# wt11_breakout_board_v10.net
KiCad netlist of a schematic drawn in EAGLE
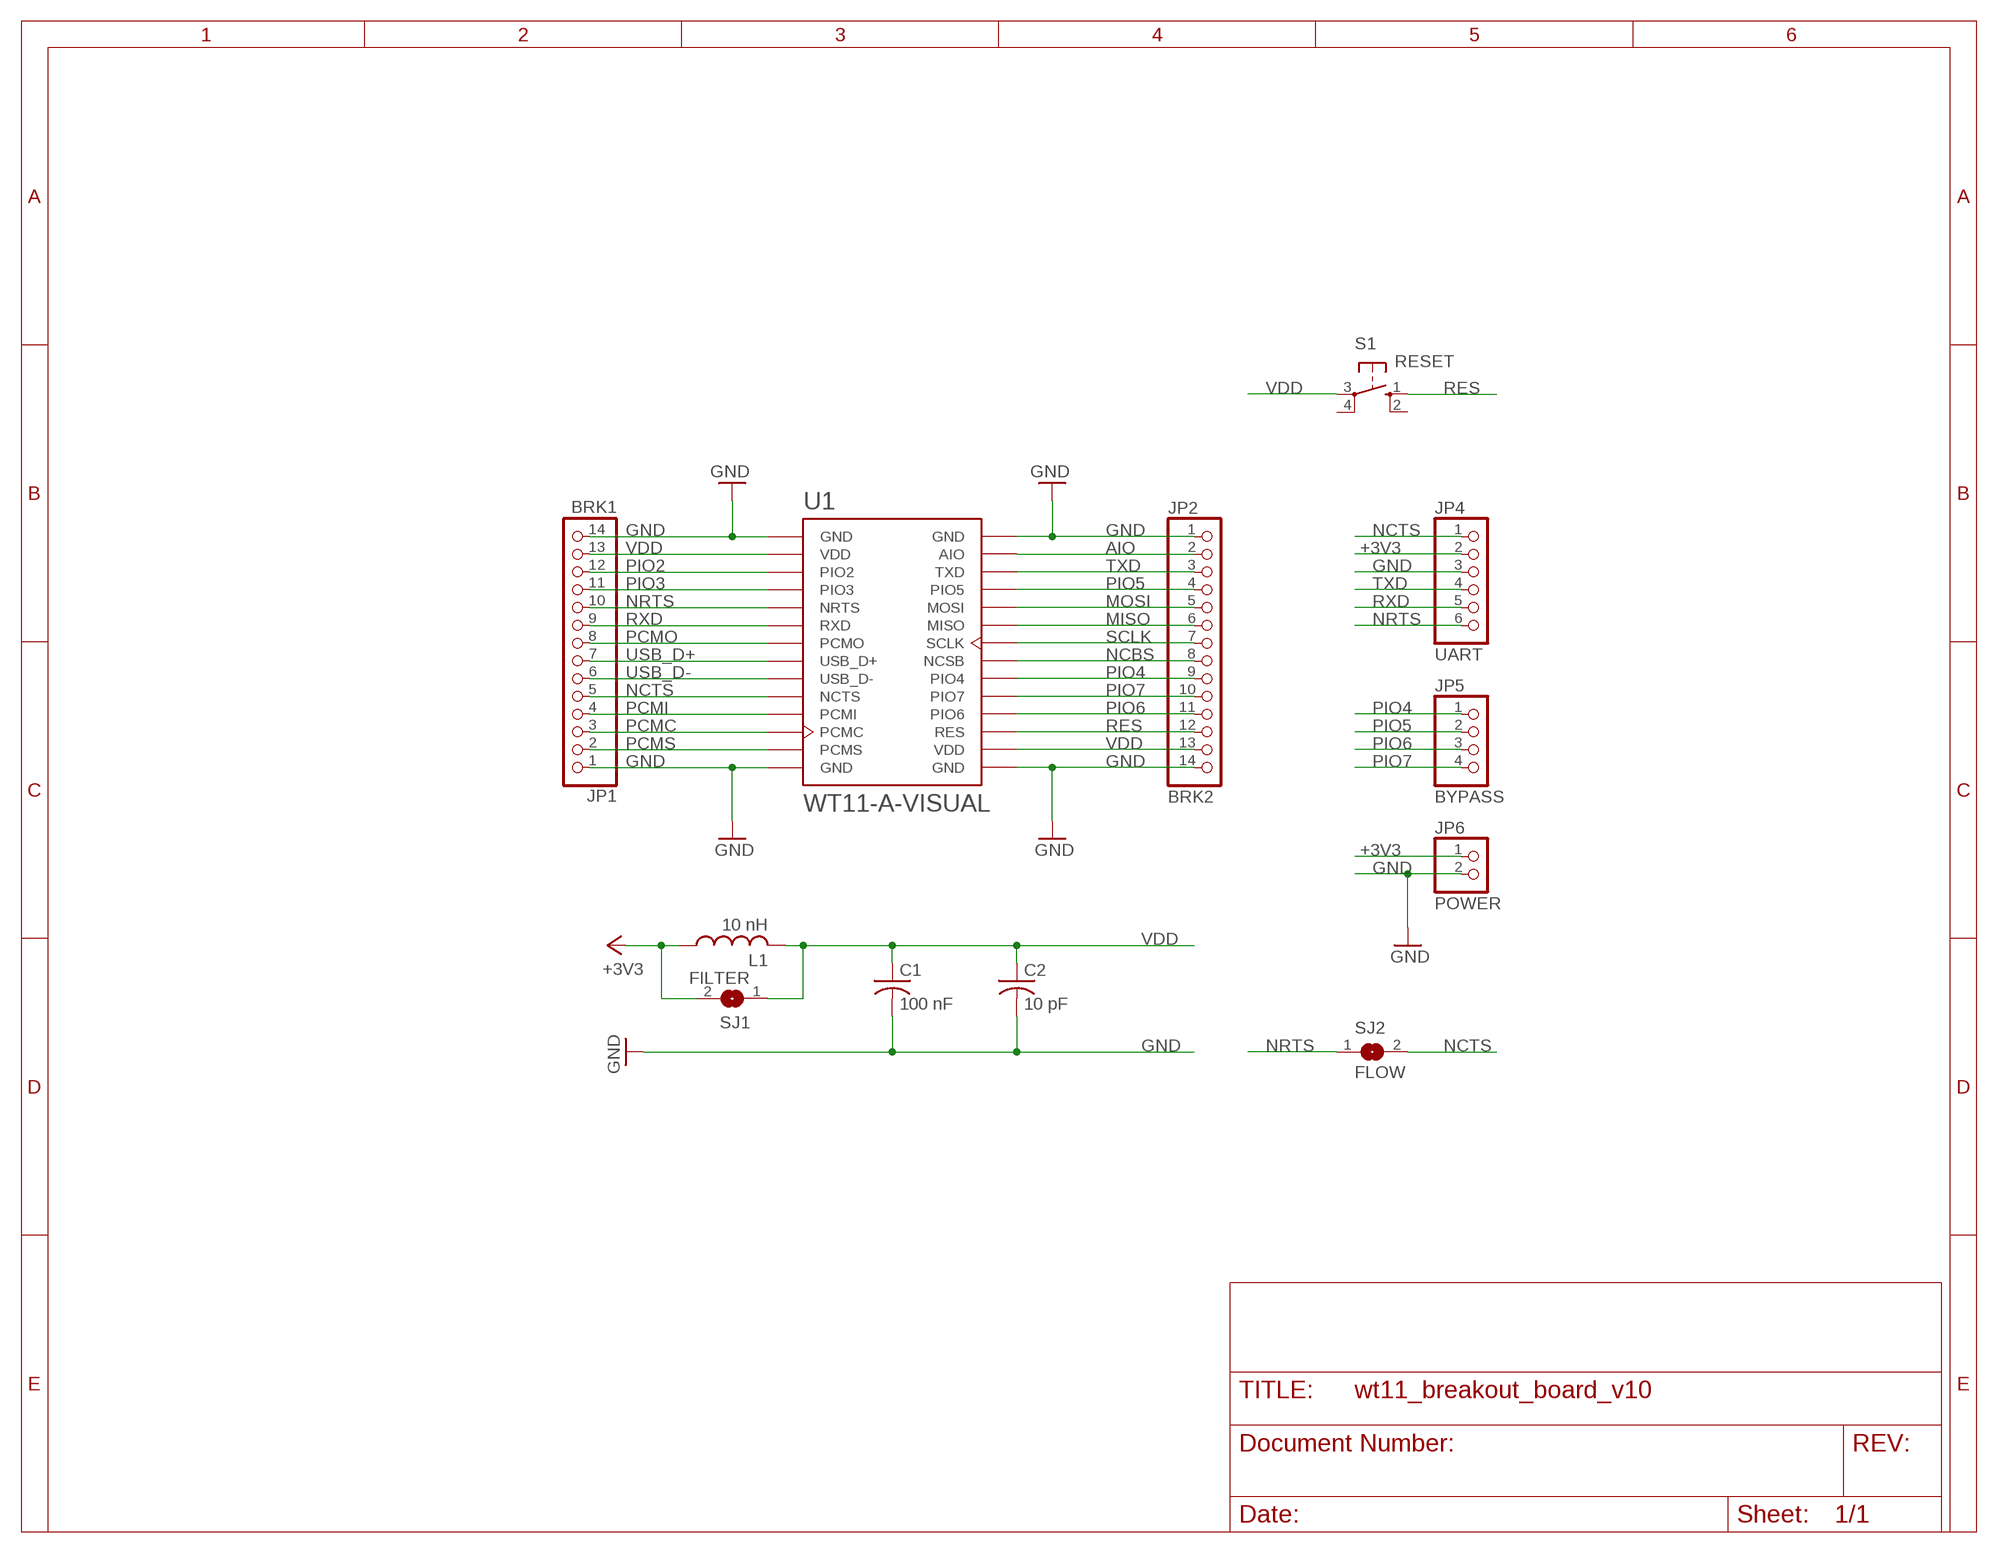
[diagram p0: schematic, sheet 1]

(export (version "E")
  (design (tool "Eeschema 10.0.6"))
  (components
    (comp (ref "C1")
      (value "100 nF")
      (footprint "eagle-import:C025-025X050")
      (libsource (lib "eagle-import") (part "C-US025-025X050"))
    )
    (comp (ref "C2")
      (value "10 pF")
      (footprint "eagle-import:C025-025X050")
      (libsource (lib "eagle-import") (part "C-US025-025X050"))
    )
    (comp (ref "JP1")
      (value "BRK1")
      (footprint "eagle-import:1X14")
      (libsource (lib "eagle-import") (part "PINHD-1X14"))
    )
    (comp (ref "JP2")
      (value "BRK2")
      (footprint "eagle-import:1X14")
      (libsource (lib "eagle-import") (part "PINHD-1X14"))
    )
    (comp (ref "JP4")
      (value "UART")
      (footprint "eagle-import:1X06")
      (libsource (lib "eagle-import") (part "PINHD-1X6"))
    )
    (comp (ref "JP5")
      (value "BYPASS")
      (footprint "eagle-import:1X04")
      (libsource (lib "eagle-import") (part "PINHD-1X4"))
    )
    (comp (ref "JP6")
      (value "POWER")
      (footprint "eagle-import:1X02")
      (libsource (lib "eagle-import") (part "PINHD-1X2"))
    )
    (comp (ref "L1")
      (value "10 nH")
      (footprint "eagle-import:0204_7")
      (libsource (lib "eagle-import") (part "L-US0204/7"))
    )
    (comp (ref "S1")
      (value "RESET")
      (footprint "eagle-import:B3F-10XX")
      (fields (field (name "MPN") "B3F-1000"))
      (libsource (lib "eagle-import") (part "10-XX"))
    )
    (comp (ref "SJ1")
      (value "FILTER")
      (footprint "eagle-import:SJ")
      (libsource (lib "eagle-import") (part "SJ"))
    )
    (comp (ref "SJ2")
      (value "FLOW")
      (footprint "eagle-import:SJ")
      (libsource (lib "eagle-import") (part "SJ"))
    )
    (comp (ref "U1")
      (value "WT11-A-VISUAL")
      (footprint "eagle-import:WT11-A")
      (libsource (lib "eagle-import") (part "WT11-A-VISUAL"))
    )
  )
  (nets
    (net (code "1") (name "+3V3") (class "Default")
      (node (ref "JP4") (pin "2") (pinfunction "2_2") (pintype "passive"))
      (node (ref "JP6") (pin "1") (pinfunction "1_1") (pintype "passive"))
      (node (ref "L1") (pin "1") (pinfunction "1_1") (pintype "passive"))
      (node (ref "SJ1") (pin "2") (pinfunction "2_2") (pintype "passive"))
    )
    (net (code "2") (name "/AIO") (class "Default")
      (node (ref "JP2") (pin "2") (pinfunction "2_2") (pintype "passive"))
      (node (ref "U1") (pin "AIO") (pinfunction "AIO_AIO") (pintype "bidirectional"))
    )
    (net (code "3") (name "/MISO") (class "Default")
      (node (ref "JP2") (pin "6") (pinfunction "6_6") (pintype "passive"))
      (node (ref "U1") (pin "MISO") (pinfunction "MISO_MISO") (pintype "output"))
    )
    (net (code "4") (name "/MOSI") (class "Default")
      (node (ref "JP2") (pin "5") (pinfunction "5_5") (pintype "passive"))
      (node (ref "U1") (pin "MOSI") (pinfunction "MOSI_MOSI") (pintype "input"))
    )
    (net (code "5") (name "/NCBS") (class "Default")
      (node (ref "JP2") (pin "8") (pinfunction "8_8") (pintype "passive"))
      (node (ref "U1") (pin "NCSB") (pinfunction "NCSB_NCSB") (pintype "input"))
    )
    (net (code "6") (name "/NCTS") (class "Default")
      (node (ref "JP1") (pin "5") (pinfunction "5_5") (pintype "passive"))
      (node (ref "JP4") (pin "1") (pinfunction "1_1") (pintype "passive"))
      (node (ref "SJ2") (pin "2") (pinfunction "2_2") (pintype "passive"))
      (node (ref "U1") (pin "NCTS") (pinfunction "NCTS_NCTS") (pintype "input"))
    )
    (net (code "7") (name "/NRTS") (class "Default")
      (node (ref "JP1") (pin "10") (pinfunction "10_10") (pintype "passive"))
      (node (ref "JP4") (pin "6") (pinfunction "6_6") (pintype "passive"))
      (node (ref "SJ2") (pin "1") (pinfunction "1_1") (pintype "passive"))
      (node (ref "U1") (pin "NRTS") (pinfunction "NRTS_NRTS") (pintype "output"))
    )
    (net (code "8") (name "/PCMC") (class "Default")
      (node (ref "JP1") (pin "3") (pinfunction "3_3") (pintype "passive"))
      (node (ref "U1") (pin "PCMC") (pinfunction "PCMC_PCMC") (pintype "bidirectional"))
    )
    (net (code "9") (name "/PCMI") (class "Default")
      (node (ref "JP1") (pin "4") (pinfunction "4_4") (pintype "passive"))
      (node (ref "U1") (pin "PCMI") (pinfunction "PCMI_PCMI") (pintype "input"))
    )
    (net (code "10") (name "/PCMO") (class "Default")
      (node (ref "JP1") (pin "8") (pinfunction "8_8") (pintype "passive"))
      (node (ref "U1") (pin "PCMO") (pinfunction "PCMO_PCMO") (pintype "output"))
    )
    (net (code "11") (name "/PCMS") (class "Default")
      (node (ref "JP1") (pin "2") (pinfunction "2_2") (pintype "passive"))
      (node (ref "U1") (pin "PCMS") (pinfunction "PCMS_PCMS") (pintype "bidirectional"))
    )
    (net (code "12") (name "/PIO2") (class "Default")
      (node (ref "JP1") (pin "12") (pinfunction "12_12") (pintype "passive"))
      (node (ref "U1") (pin "PIO2") (pinfunction "PIO2_PIO2") (pintype "bidirectional"))
    )
    (net (code "13") (name "/PIO3") (class "Default")
      (node (ref "JP1") (pin "11") (pinfunction "11_11") (pintype "passive"))
      (node (ref "U1") (pin "PIO3") (pinfunction "PIO3_PIO3") (pintype "bidirectional"))
    )
    (net (code "14") (name "/PIO4") (class "Default")
      (node (ref "JP2") (pin "9") (pinfunction "9_9") (pintype "passive"))
      (node (ref "JP5") (pin "1") (pinfunction "1_1") (pintype "passive"))
      (node (ref "U1") (pin "PIO4") (pinfunction "PIO4_PIO4") (pintype "bidirectional"))
    )
    (net (code "15") (name "/PIO5") (class "Default")
      (node (ref "JP2") (pin "4") (pinfunction "4_4") (pintype "passive"))
      (node (ref "JP5") (pin "2") (pinfunction "2_2") (pintype "passive"))
      (node (ref "U1") (pin "PIO5") (pinfunction "PIO5_PIO5") (pintype "bidirectional"))
    )
    (net (code "16") (name "/PIO6") (class "Default")
      (node (ref "JP2") (pin "11") (pinfunction "11_11") (pintype "passive"))
      (node (ref "JP5") (pin "3") (pinfunction "3_3") (pintype "passive"))
      (node (ref "U1") (pin "PIO6") (pinfunction "PIO6_PIO6") (pintype "bidirectional"))
    )
    (net (code "17") (name "/PIO7") (class "Default")
      (node (ref "JP2") (pin "10") (pinfunction "10_10") (pintype "passive"))
      (node (ref "JP5") (pin "4") (pinfunction "4_4") (pintype "passive"))
      (node (ref "U1") (pin "PIO7") (pinfunction "PIO7_PIO7") (pintype "bidirectional"))
    )
    (net (code "18") (name "/RES") (class "Default")
      (node (ref "JP2") (pin "12") (pinfunction "12_12") (pintype "passive"))
      (node (ref "S1") (pin "1") (pinfunction "S_1") (pintype "passive"))
      (node (ref "U1") (pin "RES") (pinfunction "RES_RES") (pintype "input"))
    )
    (net (code "19") (name "/RXD") (class "Default")
      (node (ref "JP1") (pin "9") (pinfunction "9_9") (pintype "passive"))
      (node (ref "JP4") (pin "5") (pinfunction "5_5") (pintype "passive"))
      (node (ref "U1") (pin "RXD") (pinfunction "RXD_RXD") (pintype "input"))
    )
    (net (code "20") (name "/SCLK") (class "Default")
      (node (ref "JP2") (pin "7") (pinfunction "7_7") (pintype "passive"))
      (node (ref "U1") (pin "SCLK") (pinfunction "SCLK_SCLK") (pintype "input"))
    )
    (net (code "21") (name "/TXD") (class "Default")
      (node (ref "JP2") (pin "3") (pinfunction "3_3") (pintype "passive"))
      (node (ref "JP4") (pin "4") (pinfunction "4_4") (pintype "passive"))
      (node (ref "U1") (pin "TXD") (pinfunction "TXD_TXD") (pintype "output"))
    )
    (net (code "22") (name "/USB_D+") (class "Default")
      (node (ref "JP1") (pin "7") (pinfunction "7_7") (pintype "passive"))
      (node (ref "U1") (pin "USB_D+") (pinfunction "USB_D+_USB_D+") (pintype "bidirectional"))
    )
    (net (code "23") (name "/USB_D-") (class "Default")
      (node (ref "JP1") (pin "6") (pinfunction "6_6") (pintype "passive"))
      (node (ref "U1") (pin "USB_D-") (pinfunction "USB_D-_USB_D-") (pintype "bidirectional"))
    )
    (net (code "24") (name "/VDD") (class "Default")
      (node (ref "C1") (pin "1") (pinfunction "1_1") (pintype "passive"))
      (node (ref "C2") (pin "1") (pinfunction "1_1") (pintype "passive"))
      (node (ref "JP1") (pin "13") (pinfunction "13_13") (pintype "passive"))
      (node (ref "JP2") (pin "13") (pinfunction "13_13") (pintype "passive"))
      (node (ref "L1") (pin "2") (pinfunction "2_2") (pintype "passive"))
      (node (ref "S1") (pin "3") (pinfunction "P_3") (pintype "passive"))
      (node (ref "SJ1") (pin "1") (pinfunction "1_1") (pintype "passive"))
      (node (ref "U1") (pin "VDD1") (pinfunction "VDD_VDD1") (pintype "power_in"))
      (node (ref "U1") (pin "VDD2") (pinfunction "VDD_VDD2") (pintype "power_in"))
    )
    (net (code "25") (name "GND") (class "Default")
      (node (ref "C1") (pin "2") (pinfunction "2_2") (pintype "passive"))
      (node (ref "C2") (pin "2") (pinfunction "2_2") (pintype "passive"))
      (node (ref "JP1") (pin "1") (pinfunction "1_1") (pintype "passive"))
      (node (ref "JP1") (pin "14") (pinfunction "14_14") (pintype "passive"))
      (node (ref "JP2") (pin "1") (pinfunction "1_1") (pintype "passive"))
      (node (ref "JP2") (pin "14") (pinfunction "14_14") (pintype "passive"))
      (node (ref "JP4") (pin "3") (pinfunction "3_3") (pintype "passive"))
      (node (ref "JP6") (pin "2") (pinfunction "2_2") (pintype "passive"))
      (node (ref "U1") (pin "GND1") (pinfunction "GND_GND1") (pintype "power_in"))
      (node (ref "U1") (pin "GND2") (pinfunction "GND_GND2") (pintype "power_in"))
      (node (ref "U1") (pin "GND3") (pinfunction "GND_GND3") (pintype "power_in"))
      (node (ref "U1") (pin "GND4") (pinfunction "GND_GND4") (pintype "power_in"))
    )
    (net (code "26") (name "unconnected-(S1-P1-Pad4)") (class "Default")
      (node (ref "S1") (pin "4") (pinfunction "P1_4") (pintype "passive"))
    )
    (net (code "27") (name "unconnected-(S1-S1-Pad2)") (class "Default")
      (node (ref "S1") (pin "2") (pinfunction "S1_2") (pintype "passive"))
    )
  )
)
